# POWER.net
KiCad netlist of a schematic drawn in Altium Designer
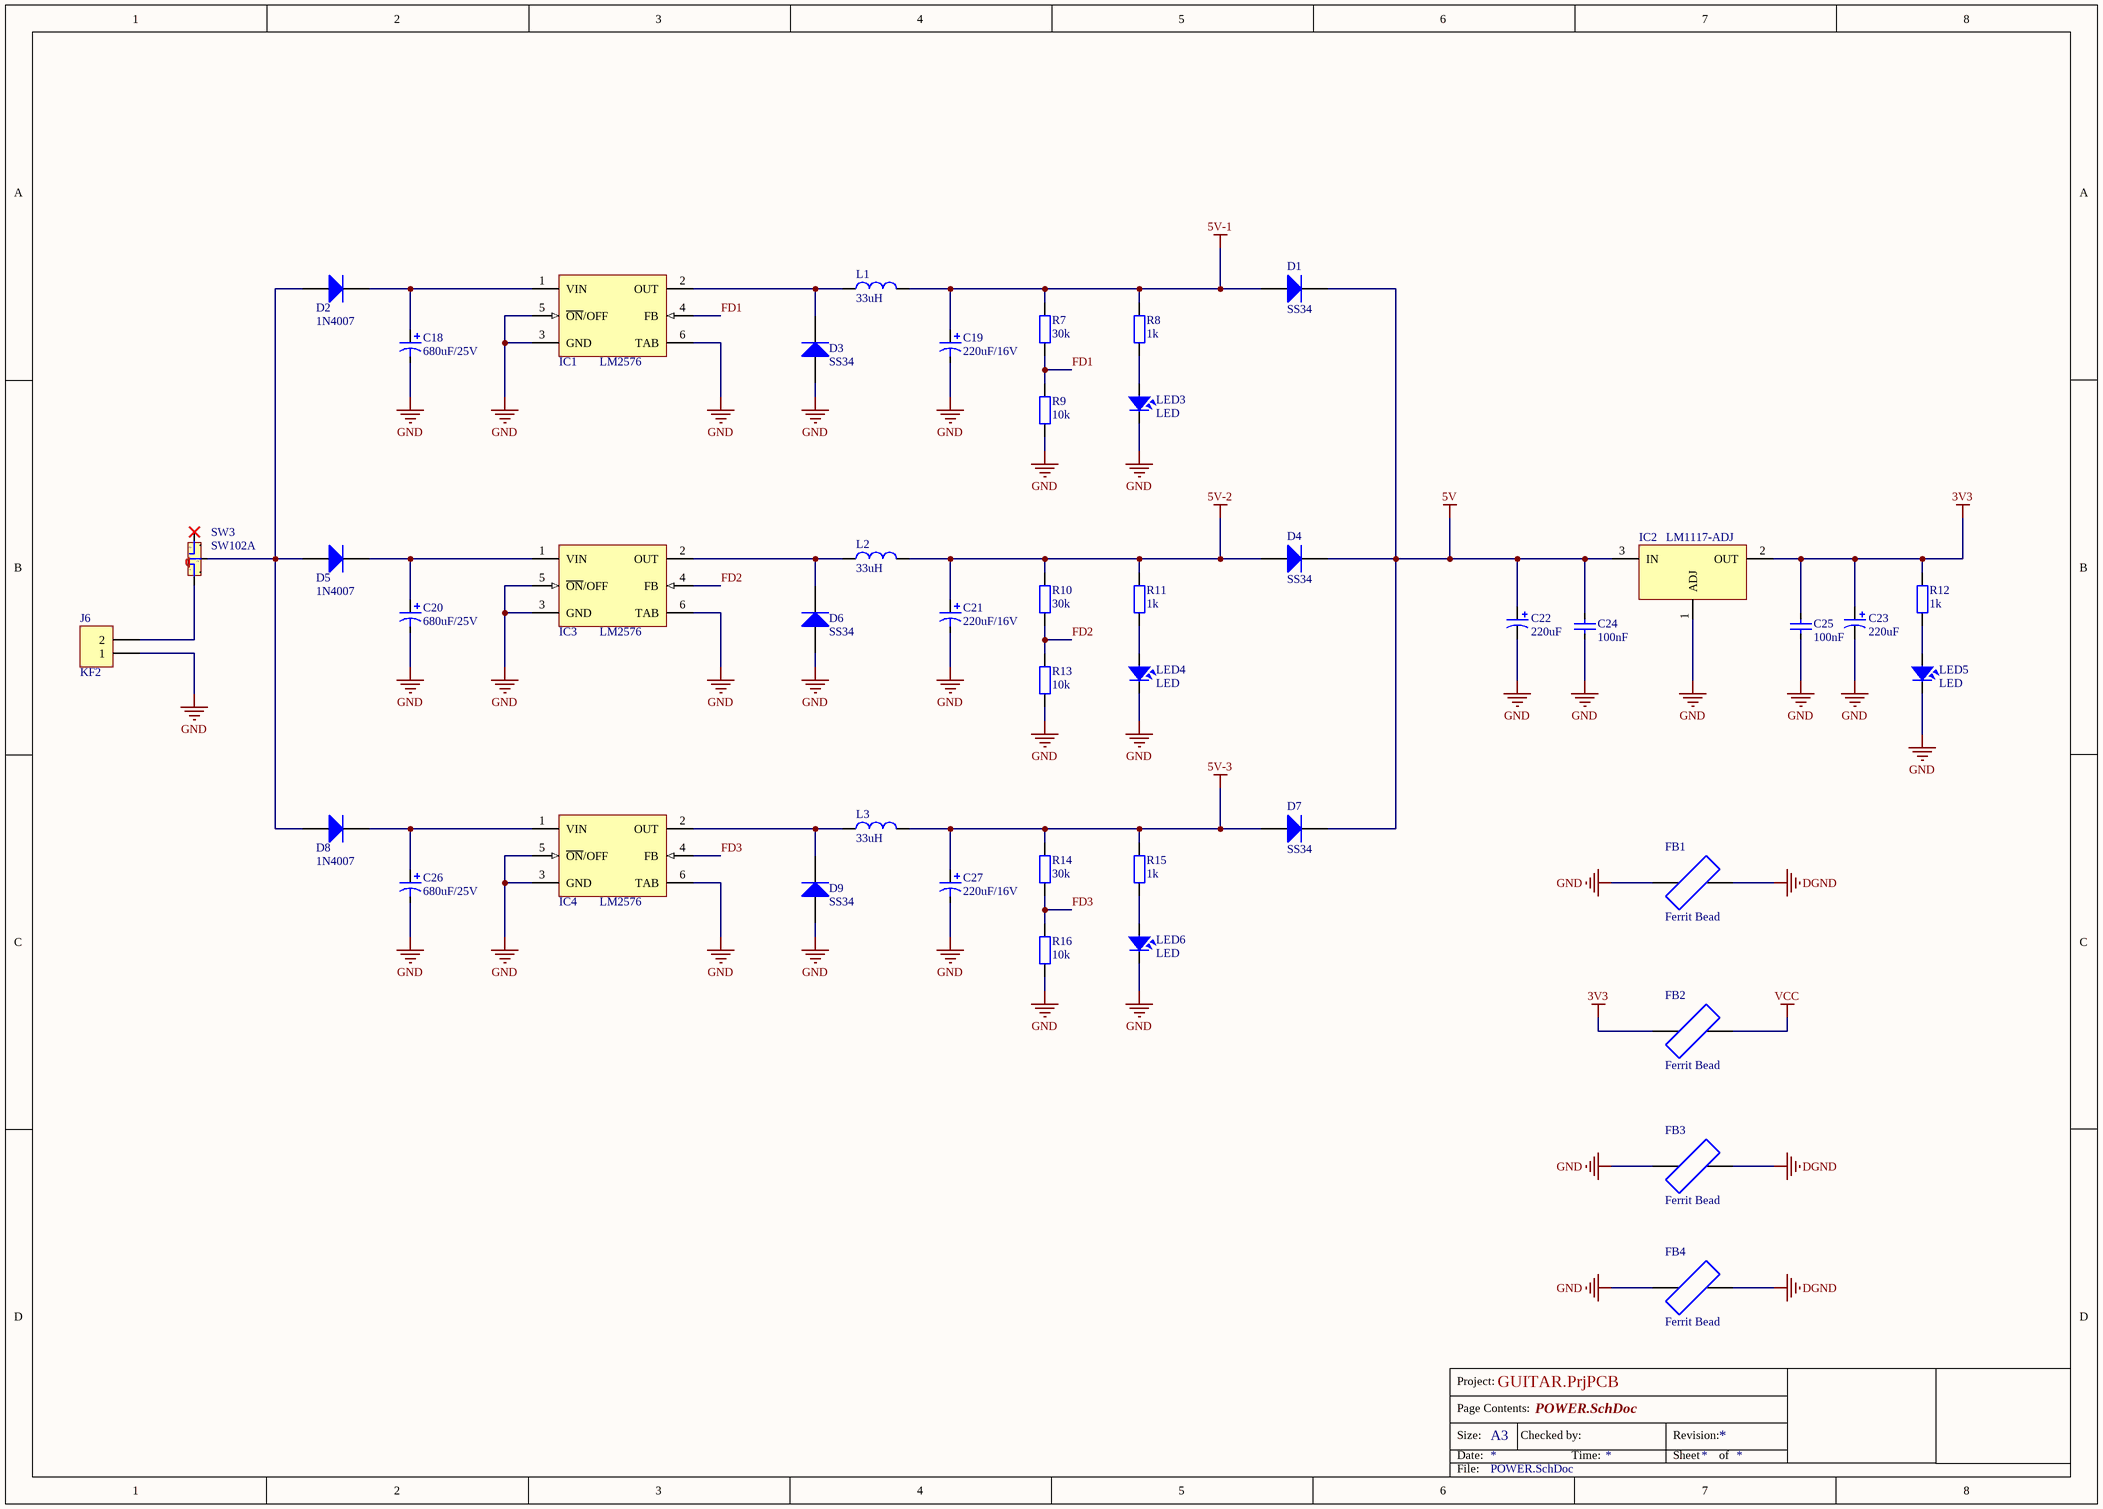
[diagram p0: POWER.SchDoc]

(export (version "E")
  (design (tool "Eeschema 10.0.6"))
  (components
    (comp (ref "C18")
      (value "680uF/25V")
      (footprint "C10mm")
      (description "Polarized Capacitor (Axial)")
      (fields (field (name "PUBLISHER") "Altium Limited"))
      (libsource (lib "My Library") (part "Cap Pol"))
    )
    (comp (ref "C19")
      (value "220uF/16V")
      (footprint "C5mm")
      (description "Polarized Capacitor (Axial)")
      (fields (field (name "PUBLISHER") "Altium Limited"))
      (libsource (lib "My Library") (part "Cap Pol"))
    )
    (comp (ref "C20")
      (value "680uF/25V")
      (footprint "C10mm")
      (description "Polarized Capacitor (Axial)")
      (fields (field (name "PUBLISHER") "Altium Limited"))
      (libsource (lib "My Library") (part "Cap Pol"))
    )
    (comp (ref "C21")
      (value "220uF/16V")
      (footprint "C5mm")
      (description "Polarized Capacitor (Axial)")
      (fields (field (name "PUBLISHER") "Altium Limited"))
      (libsource (lib "My Library") (part "Cap Pol"))
    )
    (comp (ref "C22")
      (value "220uF")
      (footprint "CAP_7343")
      (description "Polazied Tantalum Capacitor")
      (libsource (lib "My Library") (part "CAP_TAN_SMD"))
    )
    (comp (ref "C23")
      (value "220uF")
      (footprint "CAP_7343")
      (description "Polazied Tantalum Capacitor")
      (libsource (lib "My Library") (part "CAP_TAN_SMD"))
    )
    (comp (ref "C24")
      (value "100nF")
      (footprint "CAP_0805")
      (description "Capacitor")
      (fields (field (name "PUBLISHER") "Altium Limited"))
      (libsource (lib "My Library") (part "CapSMD"))
    )
    (comp (ref "C25")
      (value "100nF")
      (footprint "CAP_0805")
      (description "Capacitor")
      (fields (field (name "PUBLISHER") "Altium Limited"))
      (libsource (lib "My Library") (part "CapSMD"))
    )
    (comp (ref "C26")
      (value "680uF/25V")
      (footprint "C10mm")
      (description "Polarized Capacitor (Axial)")
      (fields (field (name "PUBLISHER") "Altium Limited"))
      (libsource (lib "My Library") (part "Cap Pol"))
    )
    (comp (ref "C27")
      (value "220uF/16V")
      (footprint "C5mm")
      (description "Polarized Capacitor (Axial)")
      (fields (field (name "PUBLISHER") "Altium Limited"))
      (libsource (lib "My Library") (part "Cap Pol"))
    )
    (comp (ref "D1")
      (value "SS34")
      (footprint "DO-214AC(SMA)")
      (description "Default Diode")
      (fields (field (name "PUBLISHER") "Altium Limited"))
      (libsource (lib "My Library") (part "Diode SMD"))
    )
    (comp (ref "D2")
      (value "1N4007")
      (footprint "DO-214AC(SMA)")
      (description "Default Diode")
      (fields (field (name "PUBLISHER") "Altium Limited"))
      (libsource (lib "My Library") (part "Diode SMD"))
    )
    (comp (ref "D3")
      (value "SS34")
      (footprint "DO-214AC(SMA)")
      (description "Default Diode")
      (fields (field (name "PUBLISHER") "Altium Limited"))
      (libsource (lib "My Library") (part "Diode SMD"))
    )
    (comp (ref "D4")
      (value "SS34")
      (footprint "DO-214AC(SMA)")
      (description "Default Diode")
      (fields (field (name "PUBLISHER") "Altium Limited"))
      (libsource (lib "My Library") (part "Diode SMD"))
    )
    (comp (ref "D5")
      (value "1N4007")
      (footprint "DO-214AC(SMA)")
      (description "Default Diode")
      (fields (field (name "PUBLISHER") "Altium Limited"))
      (libsource (lib "My Library") (part "Diode SMD"))
    )
    (comp (ref "D6")
      (value "SS34")
      (footprint "DO-214AC(SMA)")
      (description "Default Diode")
      (fields (field (name "PUBLISHER") "Altium Limited"))
      (libsource (lib "My Library") (part "Diode SMD"))
    )
    (comp (ref "D7")
      (value "SS34")
      (footprint "DO-214AC(SMA)")
      (description "Default Diode")
      (fields (field (name "PUBLISHER") "Altium Limited"))
      (libsource (lib "My Library") (part "Diode SMD"))
    )
    (comp (ref "D8")
      (value "1N4007")
      (footprint "DO-214AC(SMA)")
      (description "Default Diode")
      (fields (field (name "PUBLISHER") "Altium Limited"))
      (libsource (lib "My Library") (part "Diode SMD"))
    )
    (comp (ref "D9")
      (value "SS34")
      (footprint "DO-214AC(SMA)")
      (description "Default Diode")
      (fields (field (name "PUBLISHER") "Altium Limited"))
      (libsource (lib "My Library") (part "Diode SMD"))
    )
    (comp (ref "FB1")
      (value "Ferrit Bead")
      (footprint "RES-SMD-0805")
      (description "Generic Ferrit Bead")
      (libsource (lib "My Library") (part "Ferrit Bead"))
    )
    (comp (ref "FB2")
      (value "Ferrit Bead")
      (footprint "RES-SMD-0805")
      (description "Generic Ferrit Bead")
      (libsource (lib "My Library") (part "Ferrit Bead"))
    )
    (comp (ref "FB3")
      (value "Ferrit Bead")
      (footprint "RES-SMD-0805")
      (description "Generic Ferrit Bead")
      (libsource (lib "My Library") (part "Ferrit Bead"))
    )
    (comp (ref "FB4")
      (value "Ferrit Bead")
      (footprint "RES-SMD-0805")
      (description "Generic Ferrit Bead")
      (libsource (lib "My Library") (part "Ferrit Bead"))
    )
    (comp (ref "IC1") (value "LM2576") (footprint "TO263-5") (libsource (lib "My Library") (part "LM2576")))
    (comp (ref "IC2")
      (value "LM1117-ADJ")
      (footprint "LM1117-SOP")
      (description "800mA Low-Dropout Linear Regulator")
      (fields (field (name "CREATOR") "Nguyen Ba Bien"))
      (libsource (lib "My Library") (part "LM1117-ADJ"))
    )
    (comp (ref "IC3") (value "LM2576") (footprint "TO263-5") (libsource (lib "My Library") (part "LM2576")))
    (comp (ref "IC4") (value "LM2576") (footprint "TO263-5") (libsource (lib "My Library") (part "LM2576")))
    (comp (ref "J6")
      (value "KF2")
      (footprint "KF2-5.08T")
      (fields
        (field (name "MANUFACTURER") "Würth Elektronik eiSos GmbH")
        (field (name "PARTNO") "691103110002")
        (field (name "CREATED BY") "Karrer Zheng")
      )
      (libsource (lib "My Library") (part "KF2"))
    )
    (comp (ref "L1")
      (value "33uH")
      (footprint "L-SMD-M-12x10")
      (description "Inductor")
      (libsource (lib "My Library") (part "Inductor"))
    )
    (comp (ref "L2")
      (value "33uH")
      (footprint "L-SMD-M-12x10")
      (description "Inductor")
      (libsource (lib "My Library") (part "Inductor"))
    )
    (comp (ref "L3")
      (value "33uH")
      (footprint "L-SMD-M-12x10")
      (description "Inductor")
      (libsource (lib "My Library") (part "Inductor"))
    )
    (comp (ref "LED3")
      (value "LED")
      (footprint "LED-0805-Red")
      (description "LED Single colour Green and Red")
      (libsource (lib "My Library") (part "LED"))
    )
    (comp (ref "LED4")
      (value "LED")
      (footprint "LED-0805-Red")
      (description "LED Single colour Green and Red")
      (libsource (lib "My Library") (part "LED"))
    )
    (comp (ref "LED5")
      (value "LED")
      (footprint "LED-0805-Blue")
      (description "LED Single colour Green and Red")
      (libsource (lib "My Library") (part "LED"))
    )
    (comp (ref "LED6")
      (value "LED")
      (footprint "LED-0805-Red")
      (description "LED Single colour Green and Red")
      (libsource (lib "My Library") (part "LED"))
    )
    (comp (ref "R7")
      (value "30k")
      (footprint "RES-SMD-0805")
      (description "Resistor SMD")
      (fields
        (field (name "MANUFACTURER") "Generic Components")
        (field (name "PUBLISHER") "Altium Hobart Technology Centre")
      )
      (libsource (lib "My Library") (part "Resistor - SMD"))
    )
    (comp (ref "R8")
      (value "1k")
      (footprint "RES-SMD-0805")
      (description "Resistor SMD")
      (fields
        (field (name "MANUFACTURER") "Generic Components")
        (field (name "PUBLISHER") "Altium Hobart Technology Centre")
      )
      (libsource (lib "My Library") (part "Resistor - SMD"))
    )
    (comp (ref "R9")
      (value "10k")
      (footprint "RES-SMD-0805")
      (description "Resistor SMD")
      (fields
        (field (name "MANUFACTURER") "Generic Components")
        (field (name "PUBLISHER") "Altium Hobart Technology Centre")
      )
      (libsource (lib "My Library") (part "Resistor - SMD"))
    )
    (comp (ref "R10")
      (value "30k")
      (footprint "RES-SMD-0805")
      (description "Resistor SMD")
      (fields
        (field (name "MANUFACTURER") "Generic Components")
        (field (name "PUBLISHER") "Altium Hobart Technology Centre")
      )
      (libsource (lib "My Library") (part "Resistor - SMD"))
    )
    (comp (ref "R11")
      (value "1k")
      (footprint "RES-SMD-0805")
      (description "Resistor SMD")
      (fields
        (field (name "MANUFACTURER") "Generic Components")
        (field (name "PUBLISHER") "Altium Hobart Technology Centre")
      )
      (libsource (lib "My Library") (part "Resistor - SMD"))
    )
    (comp (ref "R12")
      (value "1k")
      (footprint "RES-SMD-0805")
      (description "Resistor SMD")
      (fields
        (field (name "MANUFACTURER") "Generic Components")
        (field (name "PUBLISHER") "Altium Hobart Technology Centre")
      )
      (libsource (lib "My Library") (part "Resistor - SMD"))
    )
    (comp (ref "R13")
      (value "10k")
      (footprint "RES-SMD-0805")
      (description "Resistor SMD")
      (fields
        (field (name "MANUFACTURER") "Generic Components")
        (field (name "PUBLISHER") "Altium Hobart Technology Centre")
      )
      (libsource (lib "My Library") (part "Resistor - SMD"))
    )
    (comp (ref "R14")
      (value "30k")
      (footprint "RES-SMD-0805")
      (description "Resistor SMD")
      (fields
        (field (name "MANUFACTURER") "Generic Components")
        (field (name "PUBLISHER") "Altium Hobart Technology Centre")
      )
      (libsource (lib "My Library") (part "Resistor - SMD"))
    )
    (comp (ref "R15")
      (value "1k")
      (footprint "RES-SMD-0805")
      (description "Resistor SMD")
      (fields
        (field (name "MANUFACTURER") "Generic Components")
        (field (name "PUBLISHER") "Altium Hobart Technology Centre")
      )
      (libsource (lib "My Library") (part "Resistor - SMD"))
    )
    (comp (ref "R16")
      (value "10k")
      (footprint "RES-SMD-0805")
      (description "Resistor SMD")
      (fields
        (field (name "MANUFACTURER") "Generic Components")
        (field (name "PUBLISHER") "Altium Hobart Technology Centre")
      )
      (libsource (lib "My Library") (part "Resistor - SMD"))
    )
    (comp (ref "SW3")
      (value "SW102A")
      (footprint "SW102")
      (description "Switch 102 on Broad")
      (libsource (lib "My Library") (part "SW102A"))
    )
  )
  (nets
    (net (code "1") (name "/FD1") (class "Default")
      (node (ref "IC1") (pin "4") (pinfunction "FB_4") (pintype "input"))
      (node (ref "R7") (pin "2") (pinfunction "2_2") (pintype "passive"))
      (node (ref "R9") (pin "1") (pinfunction "1_1") (pintype "passive"))
    )
    (net (code "2") (name "/FD2") (class "Default")
      (node (ref "IC3") (pin "4") (pinfunction "FB_4") (pintype "input"))
      (node (ref "R10") (pin "2") (pinfunction "2_2") (pintype "passive"))
      (node (ref "R13") (pin "1") (pinfunction "1_1") (pintype "passive"))
    )
    (net (code "3") (name "/FD3") (class "Default")
      (node (ref "IC4") (pin "4") (pinfunction "FB_4") (pintype "input"))
      (node (ref "R14") (pin "2") (pinfunction "2_2") (pintype "passive"))
      (node (ref "R16") (pin "1") (pinfunction "1_1") (pintype "passive"))
    )
    (net (code "4") (name "3V3") (class "Default")
      (node (ref "C23") (pin "1") (pinfunction "1_1") (pintype "passive"))
      (node (ref "C25") (pin "2") (pinfunction "2_2") (pintype "passive"))
      (node (ref "FB2") (pin "1") (pintype "passive"))
      (node (ref "IC2") (pin "2") (pinfunction "OUT_2") (pintype "passive"))
      (node (ref "R12") (pin "1") (pinfunction "1_1") (pintype "passive"))
    )
    (net (code "5") (name "5V") (class "Default")
      (node (ref "C22") (pin "1") (pinfunction "1_1") (pintype "passive"))
      (node (ref "C24") (pin "2") (pinfunction "2_2") (pintype "passive"))
      (node (ref "D1") (pin "2") (pinfunction "K_2") (pintype "passive"))
      (node (ref "D4") (pin "2") (pinfunction "K_2") (pintype "passive"))
      (node (ref "D7") (pin "2") (pinfunction "K_2") (pintype "passive"))
      (node (ref "IC2") (pin "3") (pinfunction "IN_3") (pintype "passive"))
    )
    (net (code "6") (name "5V-1") (class "Default")
      (node (ref "C19") (pin "1") (pinfunction "1_1") (pintype "passive"))
      (node (ref "D1") (pin "1") (pinfunction "A_1") (pintype "passive"))
      (node (ref "L1") (pin "2") (pinfunction "2_2") (pintype "passive"))
      (node (ref "R7") (pin "1") (pinfunction "1_1") (pintype "passive"))
      (node (ref "R8") (pin "1") (pinfunction "1_1") (pintype "passive"))
    )
    (net (code "7") (name "5V-2") (class "Default")
      (node (ref "C21") (pin "1") (pinfunction "1_1") (pintype "passive"))
      (node (ref "D4") (pin "1") (pinfunction "A_1") (pintype "passive"))
      (node (ref "L2") (pin "2") (pinfunction "2_2") (pintype "passive"))
      (node (ref "R10") (pin "1") (pinfunction "1_1") (pintype "passive"))
      (node (ref "R11") (pin "1") (pinfunction "1_1") (pintype "passive"))
    )
    (net (code "8") (name "5V-3") (class "Default")
      (node (ref "C27") (pin "1") (pinfunction "1_1") (pintype "passive"))
      (node (ref "D7") (pin "1") (pinfunction "A_1") (pintype "passive"))
      (node (ref "L3") (pin "2") (pinfunction "2_2") (pintype "passive"))
      (node (ref "R14") (pin "1") (pinfunction "1_1") (pintype "passive"))
      (node (ref "R15") (pin "1") (pinfunction "1_1") (pintype "passive"))
    )
    (net (code "9") (name "DGND") (class "Default")
      (node (ref "FB1") (pin "2") (pintype "passive"))
      (node (ref "FB3") (pin "2") (pintype "passive"))
      (node (ref "FB4") (pin "2") (pintype "passive"))
    )
    (net (code "10") (name "GND") (class "Default")
      (node (ref "C18") (pin "2") (pinfunction "2_2") (pintype "passive"))
      (node (ref "C19") (pin "2") (pinfunction "2_2") (pintype "passive"))
      (node (ref "C20") (pin "2") (pinfunction "2_2") (pintype "passive"))
      (node (ref "C21") (pin "2") (pinfunction "2_2") (pintype "passive"))
      (node (ref "C22") (pin "2") (pinfunction "2_2") (pintype "passive"))
      (node (ref "C23") (pin "2") (pinfunction "2_2") (pintype "passive"))
      (node (ref "C24") (pin "1") (pinfunction "1_1") (pintype "passive"))
      (node (ref "C25") (pin "1") (pinfunction "1_1") (pintype "passive"))
      (node (ref "C26") (pin "2") (pinfunction "2_2") (pintype "passive"))
      (node (ref "C27") (pin "2") (pinfunction "2_2") (pintype "passive"))
      (node (ref "D3") (pin "1") (pinfunction "A_1") (pintype "passive"))
      (node (ref "D6") (pin "1") (pinfunction "A_1") (pintype "passive"))
      (node (ref "D9") (pin "1") (pinfunction "A_1") (pintype "passive"))
      (node (ref "FB1") (pin "1") (pintype "passive"))
      (node (ref "FB3") (pin "1") (pintype "passive"))
      (node (ref "FB4") (pin "1") (pintype "passive"))
      (node (ref "IC1") (pin "3") (pinfunction "GND_3") (pintype "power_in"))
      (node (ref "IC1") (pin "5") (pinfunction "~{ON}/OFF_5") (pintype "input"))
      (node (ref "IC1") (pin "6") (pinfunction "TAB_6") (pintype "power_in"))
      (node (ref "IC2") (pin "1") (pinfunction "ADJ_1") (pintype "passive"))
      (node (ref "IC3") (pin "3") (pinfunction "GND_3") (pintype "power_in"))
      (node (ref "IC3") (pin "5") (pinfunction "~{ON}/OFF_5") (pintype "input"))
      (node (ref "IC3") (pin "6") (pinfunction "TAB_6") (pintype "power_in"))
      (node (ref "IC4") (pin "3") (pinfunction "GND_3") (pintype "power_in"))
      (node (ref "IC4") (pin "5") (pinfunction "~{ON}/OFF_5") (pintype "input"))
      (node (ref "IC4") (pin "6") (pinfunction "TAB_6") (pintype "power_in"))
      (node (ref "J6") (pin "1") (pinfunction "1_1") (pintype "passive"))
      (node (ref "LED3") (pin "2") (pinfunction "2_2") (pintype "passive"))
      (node (ref "LED4") (pin "2") (pinfunction "2_2") (pintype "passive"))
      (node (ref "LED5") (pin "2") (pinfunction "2_2") (pintype "passive"))
      (node (ref "LED6") (pin "2") (pinfunction "2_2") (pintype "passive"))
      (node (ref "R13") (pin "2") (pinfunction "2_2") (pintype "passive"))
      (node (ref "R16") (pin "2") (pinfunction "2_2") (pintype "passive"))
      (node (ref "R9") (pin "2") (pinfunction "2_2") (pintype "passive"))
    )
    (net (code "11") (name "Net-(D2-A)") (class "Default")
      (node (ref "D2") (pin "1") (pinfunction "A_1") (pintype "passive"))
      (node (ref "D5") (pin "1") (pinfunction "A_1") (pintype "passive"))
      (node (ref "D8") (pin "1") (pinfunction "A_1") (pintype "passive"))
      (node (ref "SW3") (pin "2") (pinfunction "2_2") (pintype "passive"))
    )
    (net (code "12") (name "Net-(D2-K)") (class "Default")
      (node (ref "C18") (pin "1") (pinfunction "1_1") (pintype "passive"))
      (node (ref "D2") (pin "2") (pinfunction "K_2") (pintype "passive"))
      (node (ref "IC1") (pin "1") (pinfunction "VIN_1") (pintype "power_in"))
    )
    (net (code "13") (name "Net-(D3-K)") (class "Default")
      (node (ref "D3") (pin "2") (pinfunction "K_2") (pintype "passive"))
      (node (ref "IC1") (pin "2") (pinfunction "OUT_2") (pintype "power_in"))
      (node (ref "L1") (pin "1") (pinfunction "1_1") (pintype "passive"))
    )
    (net (code "14") (name "Net-(D5-K)") (class "Default")
      (node (ref "C20") (pin "1") (pinfunction "1_1") (pintype "passive"))
      (node (ref "D5") (pin "2") (pinfunction "K_2") (pintype "passive"))
      (node (ref "IC3") (pin "1") (pinfunction "VIN_1") (pintype "power_in"))
    )
    (net (code "15") (name "Net-(D6-K)") (class "Default")
      (node (ref "D6") (pin "2") (pinfunction "K_2") (pintype "passive"))
      (node (ref "IC3") (pin "2") (pinfunction "OUT_2") (pintype "power_in"))
      (node (ref "L2") (pin "1") (pinfunction "1_1") (pintype "passive"))
    )
    (net (code "16") (name "Net-(D8-K)") (class "Default")
      (node (ref "C26") (pin "1") (pinfunction "1_1") (pintype "passive"))
      (node (ref "D8") (pin "2") (pinfunction "K_2") (pintype "passive"))
      (node (ref "IC4") (pin "1") (pinfunction "VIN_1") (pintype "power_in"))
    )
    (net (code "17") (name "Net-(D9-K)") (class "Default")
      (node (ref "D9") (pin "2") (pinfunction "K_2") (pintype "passive"))
      (node (ref "IC4") (pin "2") (pinfunction "OUT_2") (pintype "power_in"))
      (node (ref "L3") (pin "1") (pinfunction "1_1") (pintype "passive"))
    )
    (net (code "18") (name "Net-(J6-Pad2)") (class "Default")
      (node (ref "J6") (pin "2") (pinfunction "2_2") (pintype "passive"))
      (node (ref "SW3") (pin "1") (pinfunction "1_1") (pintype "passive"))
    )
    (net (code "19") (name "Net-(LED3-Pad1)") (class "Default")
      (node (ref "LED3") (pin "1") (pinfunction "1_1") (pintype "passive"))
      (node (ref "R8") (pin "2") (pinfunction "2_2") (pintype "passive"))
    )
    (net (code "20") (name "Net-(LED4-Pad1)") (class "Default")
      (node (ref "LED4") (pin "1") (pinfunction "1_1") (pintype "passive"))
      (node (ref "R11") (pin "2") (pinfunction "2_2") (pintype "passive"))
    )
    (net (code "21") (name "Net-(LED5-Pad1)") (class "Default")
      (node (ref "LED5") (pin "1") (pinfunction "1_1") (pintype "passive"))
      (node (ref "R12") (pin "2") (pinfunction "2_2") (pintype "passive"))
    )
    (net (code "22") (name "Net-(LED6-Pad1)") (class "Default")
      (node (ref "LED6") (pin "1") (pinfunction "1_1") (pintype "passive"))
      (node (ref "R15") (pin "2") (pinfunction "2_2") (pintype "passive"))
    )
    (net (code "23") (name "VCC") (class "Default") (node (ref "FB2") (pin "2") (pintype "passive")))
    (net (code "24") (name "unconnected-(SW3-Pad3)") (class "Default")
      (node (ref "SW3") (pin "3") (pinfunction "3_3") (pintype "passive+no_connect"))
    )
    (net (code "25") (name "unconnected-(SW3-Pad4)") (class "Default")
      (node (ref "SW3") (pin "4") (pinfunction "4_4") (pintype "passive"))
    )
    (net (code "26") (name "unconnected-(SW3-Pad5)") (class "Default")
      (node (ref "SW3") (pin "5") (pinfunction "5_5") (pintype "passive"))
    )
  )
)
